# Sheet6.net
KiCad netlist of a schematic drawn in Altium Designer
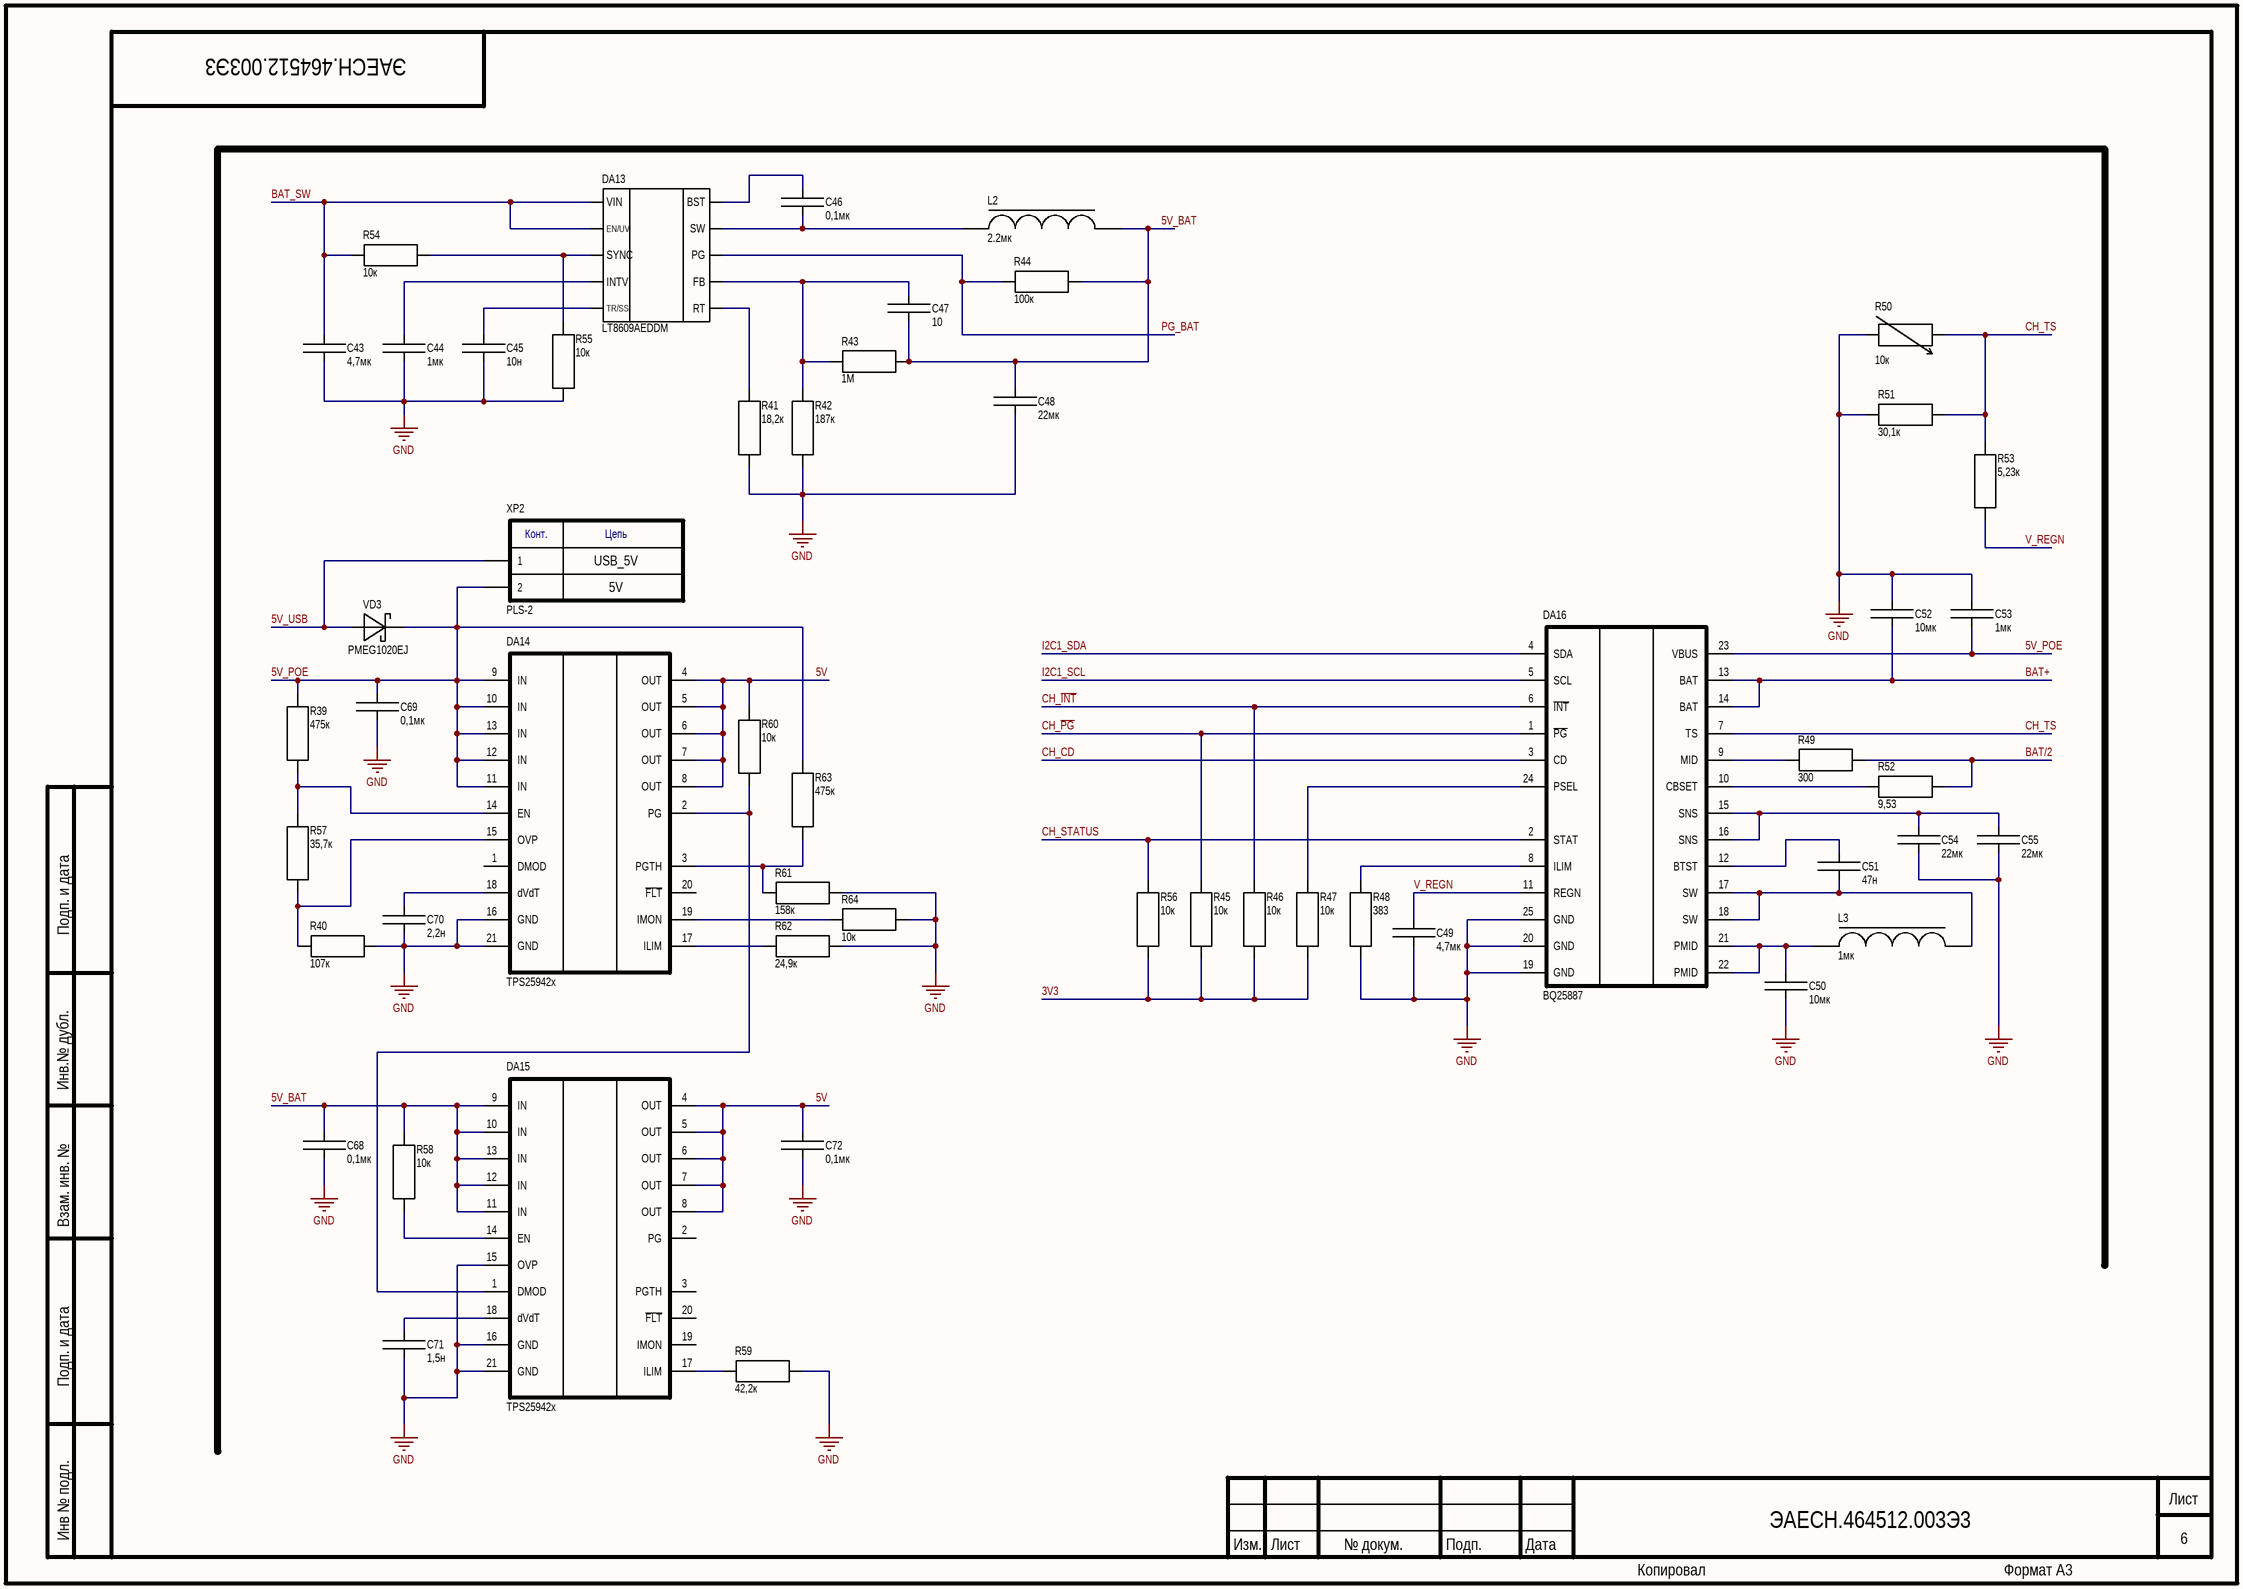
[diagram p0: Sheet6.SchDoc]

(export (version "E")
  (design (tool "Eeschema 10.0.6"))
  (components
    (comp (ref "C43")
      (value "4,7мк")
      (footprint "С0603")
      (fields (field (name "Comment") "C"))
      (libsource (lib "Schlib1") (part "C"))
    )
    (comp (ref "C44")
      (value "1мк")
      (footprint "С0603")
      (fields (field (name "Comment") "C"))
      (libsource (lib "Schlib1") (part "C"))
    )
    (comp (ref "C45")
      (value "10н")
      (footprint "С0603")
      (fields (field (name "Comment") "C"))
      (libsource (lib "Schlib1") (part "C"))
    )
    (comp (ref "C46")
      (value "0,1мк")
      (footprint "С0603")
      (fields (field (name "Comment") "C"))
      (libsource (lib "Schlib1") (part "C"))
    )
    (comp (ref "C47")
      (value "10")
      (footprint "С0603")
      (fields (field (name "Comment") "C"))
      (libsource (lib "Schlib1") (part "C"))
    )
    (comp (ref "C48")
      (value "22мк")
      (footprint "C1206")
      (fields (field (name "Comment") "C"))
      (libsource (lib "Schlib1") (part "C"))
    )
    (comp (ref "C49")
      (value "4,7мк")
      (footprint "С0603")
      (fields (field (name "Comment") "C"))
      (libsource (lib "Schlib1") (part "C"))
    )
    (comp (ref "C50")
      (value "10мк")
      (footprint "С0603")
      (fields (field (name "Comment") "C"))
      (libsource (lib "Schlib1") (part "C"))
    )
    (comp (ref "C51")
      (value "47н")
      (footprint "С0603")
      (fields (field (name "Comment") "C"))
      (libsource (lib "Schlib1") (part "C"))
    )
    (comp (ref "C52")
      (value "10мк")
      (footprint "С0603")
      (fields (field (name "Comment") "C"))
      (libsource (lib "Schlib1") (part "C"))
    )
    (comp (ref "C53")
      (value "1мк")
      (footprint "С0603")
      (fields (field (name "Comment") "C"))
      (libsource (lib "Schlib1") (part "C"))
    )
    (comp (ref "C54")
      (value "22мк")
      (footprint "C1206")
      (fields (field (name "Comment") "C"))
      (libsource (lib "Schlib1") (part "C"))
    )
    (comp (ref "C55")
      (value "22мк")
      (footprint "C1206")
      (fields (field (name "Comment") "C"))
      (libsource (lib "Schlib1") (part "C"))
    )
    (comp (ref "C68")
      (value "0,1мк")
      (footprint "С0603")
      (fields (field (name "Comment") "C"))
      (libsource (lib "Schlib1") (part "C"))
    )
    (comp (ref "C69")
      (value "0,1мк")
      (footprint "С0603")
      (fields (field (name "Comment") "C"))
      (libsource (lib "Schlib1") (part "C"))
    )
    (comp (ref "C70")
      (value "2,2н")
      (footprint "С0603")
      (fields (field (name "Comment") "C"))
      (libsource (lib "Schlib1") (part "C"))
    )
    (comp (ref "C71")
      (value "1,5н")
      (footprint "С0603")
      (fields (field (name "Comment") "C"))
      (libsource (lib "Schlib1") (part "C"))
    )
    (comp (ref "C72")
      (value "0,1мк")
      (footprint "С0603")
      (fields (field (name "Comment") "C"))
      (libsource (lib "Schlib1") (part "C"))
    )
    (comp (ref "DA13")
      (value "LT8609AEDDM")
      (footprint "SON-10")
      (libsource (lib "Schlib1") (part "LT8609AEDDM"))
    )
    (comp (ref "DA14")
      (value "TPS25942x")
      (footprint "WQFN-20")
      (libsource (lib "Schlib1") (part "TPS25942x"))
    )
    (comp (ref "DA15")
      (value "TPS25942x")
      (footprint "WQFN-20")
      (libsource (lib "Schlib1") (part "TPS25942x"))
    )
    (comp (ref "DA16") (value "BQ25887") (footprint "VQFN-24") (libsource (lib "Schlib1") (part "BQ25887")))
    (comp (ref "L2")
      (value "2.2мк")
      (footprint "IND_6.5x6.5_VISHAY")
      (fields (field (name "PARTNUMBER") "IHLP2525CZER2R2MA1"))
      (libsource (lib "Schlib1") (part "L"))
    )
    (comp (ref "L3")
      (value "1мк")
      (footprint "IND_6.5x6.5_VISHAY")
      (fields (field (name "PARTNUMBER") "IHLP2525CZER1R0M01"))
      (libsource (lib "Schlib1") (part "L"))
    )
    (comp (ref "R39")
      (value "475к")
      (footprint "R0603")
      (fields (field (name "Comment") "R"))
      (libsource (lib "Schlib1") (part "R"))
    )
    (comp (ref "R40")
      (value "107к")
      (footprint "R0603")
      (fields (field (name "Comment") "R"))
      (libsource (lib "Schlib1") (part "R"))
    )
    (comp (ref "R41")
      (value "18,2к")
      (footprint "R0603")
      (fields (field (name "Comment") "R"))
      (libsource (lib "Schlib1") (part "R"))
    )
    (comp (ref "R42")
      (value "187к")
      (footprint "R0603")
      (fields (field (name "Comment") "R"))
      (libsource (lib "Schlib1") (part "R"))
    )
    (comp (ref "R43")
      (value "1М")
      (footprint "R0603")
      (fields (field (name "Comment") "R"))
      (libsource (lib "Schlib1") (part "R"))
    )
    (comp (ref "R44")
      (value "100к")
      (footprint "R0603")
      (fields (field (name "Comment") "R"))
      (libsource (lib "Schlib1") (part "R"))
    )
    (comp (ref "R45")
      (value "10к")
      (footprint "R0603")
      (fields (field (name "Comment") "R"))
      (libsource (lib "Schlib1") (part "R"))
    )
    (comp (ref "R46")
      (value "10к")
      (footprint "R0603")
      (fields (field (name "Comment") "R"))
      (libsource (lib "Schlib1") (part "R"))
    )
    (comp (ref "R47")
      (value "10к")
      (footprint "R0603")
      (fields (field (name "Comment") "R"))
      (libsource (lib "Schlib1") (part "R"))
    )
    (comp (ref "R48")
      (value "383")
      (footprint "R0603")
      (fields (field (name "Comment") "R"))
      (libsource (lib "Schlib1") (part "R"))
    )
    (comp (ref "R49")
      (value "300")
      (footprint "R0603")
      (fields (field (name "Comment") "R"))
      (libsource (lib "Schlib1") (part "R"))
    )
    (comp (ref "R50")
      (value "10к")
      (footprint "R0603")
      (fields (field (name "Comment") "EWTF03-103H3T-N"))
      (libsource (lib "Schlib1") (part "R_term_n"))
    )
    (comp (ref "R51")
      (value "30,1к")
      (footprint "R0603")
      (fields (field (name "Comment") "R"))
      (libsource (lib "Schlib1") (part "R"))
    )
    (comp (ref "R52")
      (value "9,53")
      (footprint "R0603")
      (fields (field (name "Comment") "R"))
      (libsource (lib "Schlib1") (part "R"))
    )
    (comp (ref "R53")
      (value "5,23к")
      (footprint "R0603")
      (fields (field (name "Comment") "R"))
      (libsource (lib "Schlib1") (part "R"))
    )
    (comp (ref "R54")
      (value "10к")
      (footprint "R0603")
      (fields (field (name "Comment") "R"))
      (libsource (lib "Schlib1") (part "R"))
    )
    (comp (ref "R55")
      (value "10к")
      (footprint "R0603")
      (fields (field (name "Comment") "R"))
      (libsource (lib "Schlib1") (part "R"))
    )
    (comp (ref "R56")
      (value "10к")
      (footprint "R0603")
      (fields (field (name "Comment") "R"))
      (libsource (lib "Schlib1") (part "R"))
    )
    (comp (ref "R57")
      (value "35,7к")
      (footprint "R0603")
      (fields (field (name "Comment") "R"))
      (libsource (lib "Schlib1") (part "R"))
    )
    (comp (ref "R58")
      (value "10к")
      (footprint "R0603")
      (fields (field (name "Comment") "R"))
      (libsource (lib "Schlib1") (part "R"))
    )
    (comp (ref "R59")
      (value "42,2к")
      (footprint "R0603")
      (fields (field (name "Comment") "R"))
      (libsource (lib "Schlib1") (part "R"))
    )
    (comp (ref "R60")
      (value "10к")
      (footprint "R0603")
      (fields (field (name "Comment") "R"))
      (libsource (lib "Schlib1") (part "R"))
    )
    (comp (ref "R61")
      (value "158к")
      (footprint "R0603")
      (fields (field (name "Comment") "R"))
      (libsource (lib "Schlib1") (part "R"))
    )
    (comp (ref "R62")
      (value "24,9к")
      (footprint "R0603")
      (fields (field (name "Comment") "R"))
      (libsource (lib "Schlib1") (part "R"))
    )
    (comp (ref "R63")
      (value "475к")
      (footprint "R0603")
      (fields (field (name "Comment") "R"))
      (libsource (lib "Schlib1") (part "R"))
    )
    (comp (ref "R64")
      (value "10к")
      (footprint "R0603")
      (fields (field (name "Comment") "R"))
      (libsource (lib "Schlib1") (part "R"))
    )
    (comp (ref "VD3") (value "PMEG1020EJ") (footprint "SOD323F") (libsource (lib "Schlib1") (part "VD_sh")))
    (comp (ref "XP2") (value "PLS-2") (footprint "PLS-2") (libsource (lib "Schlib1") (part "2pin")))
  )
  (nets
    (net (code "1") (name "/3V3") (class "Default")
      (node (ref "R45") (pin "2") (pinfunction "2_2") (pintype "passive"))
      (node (ref "R46") (pin "2") (pinfunction "2_2") (pintype "passive"))
      (node (ref "R47") (pin "2") (pinfunction "2_2") (pintype "passive"))
      (node (ref "R56") (pin "2") (pinfunction "2_2") (pintype "passive"))
    )
    (net (code "2") (name "/5V") (class "Default")
      (node (ref "C72") (pin "1") (pinfunction "1_1") (pintype "passive"))
      (node (ref "DA14") (pin "4") (pinfunction "OUT_4") (pintype "passive"))
      (node (ref "DA14") (pin "5") (pinfunction "OUT_5") (pintype "passive"))
      (node (ref "DA14") (pin "6") (pinfunction "OUT_6") (pintype "passive"))
      (node (ref "DA14") (pin "7") (pinfunction "OUT_7") (pintype "passive"))
      (node (ref "DA14") (pin "8") (pinfunction "OUT_8") (pintype "passive"))
      (node (ref "DA15") (pin "4") (pinfunction "OUT_4") (pintype "passive"))
      (node (ref "DA15") (pin "5") (pinfunction "OUT_5") (pintype "passive"))
      (node (ref "DA15") (pin "6") (pinfunction "OUT_6") (pintype "passive"))
      (node (ref "DA15") (pin "7") (pinfunction "OUT_7") (pintype "passive"))
      (node (ref "DA15") (pin "8") (pinfunction "OUT_8") (pintype "passive"))
      (node (ref "R60") (pin "2") (pinfunction "2_2") (pintype "passive"))
    )
    (net (code "3") (name "/5V_BAT") (class "Default")
      (node (ref "C47") (pin "1") (pinfunction "1_1") (pintype "passive"))
      (node (ref "C48") (pin "1") (pinfunction "1_1") (pintype "passive"))
      (node (ref "C68") (pin "1") (pinfunction "1_1") (pintype "passive"))
      (node (ref "DA15") (pin "10") (pinfunction "IN_10") (pintype "passive"))
      (node (ref "DA15") (pin "11") (pinfunction "IN_11") (pintype "passive"))
      (node (ref "DA15") (pin "12") (pinfunction "IN_12") (pintype "passive"))
      (node (ref "DA15") (pin "13") (pinfunction "IN_13") (pintype "passive"))
      (node (ref "DA15") (pin "9") (pinfunction "IN_9") (pintype "passive"))
      (node (ref "L2") (pin "1") (pinfunction "1_1") (pintype "passive"))
      (node (ref "R43") (pin "2") (pinfunction "2_2") (pintype "passive"))
      (node (ref "R44") (pin "1") (pinfunction "1_1") (pintype "passive"))
      (node (ref "R58") (pin "2") (pinfunction "2_2") (pintype "passive"))
    )
    (net (code "4") (name "/5V_POE") (class "Default")
      (node (ref "C53") (pin "2") (pinfunction "2_2") (pintype "passive"))
      (node (ref "C69") (pin "1") (pinfunction "1_1") (pintype "passive"))
      (node (ref "DA14") (pin "10") (pinfunction "IN_10") (pintype "passive"))
      (node (ref "DA14") (pin "11") (pinfunction "IN_11") (pintype "passive"))
      (node (ref "DA14") (pin "12") (pinfunction "IN_12") (pintype "passive"))
      (node (ref "DA14") (pin "13") (pinfunction "IN_13") (pintype "passive"))
      (node (ref "DA14") (pin "9") (pinfunction "IN_9") (pintype "passive"))
      (node (ref "DA16") (pin "23") (pinfunction "VBUS_23") (pintype "passive"))
      (node (ref "R39") (pin "2") (pinfunction "2_2") (pintype "passive"))
      (node (ref "R63") (pin "2") (pinfunction "2_2") (pintype "passive"))
      (node (ref "VD3") (pin "1") (pinfunction "C_1") (pintype "passive"))
      (node (ref "XP2") (pin "2") (pinfunction "2_2") (pintype "passive"))
    )
    (net (code "5") (name "/5V_USB") (class "Default")
      (node (ref "VD3") (pin "2") (pinfunction "A_2") (pintype "passive"))
      (node (ref "XP2") (pin "1") (pinfunction "1_1") (pintype "passive"))
    )
    (net (code "6") (name "/BAT+") (class "Default")
      (node (ref "C52") (pin "2") (pinfunction "2_2") (pintype "passive"))
      (node (ref "DA16") (pin "13") (pinfunction "BAT_13") (pintype "passive"))
      (node (ref "DA16") (pin "14") (pinfunction "BAT_14") (pintype "passive"))
    )
    (net (code "7") (name "/BAT_SW") (class "Default")
      (node (ref "C43") (pin "1") (pinfunction "1_1") (pintype "passive"))
      (node (ref "DA13") (pin "10") (pinfunction "EN/UV_10") (pintype "passive"))
      (node (ref "DA13") (pin "9") (pinfunction "VIN_9") (pintype "passive"))
      (node (ref "R54") (pin "1") (pinfunction "1_1") (pintype "passive"))
    )
    (net (code "8") (name "/BAT{slash}2") (class "Default")
      (node (ref "R49") (pin "2") (pinfunction "2_2") (pintype "passive"))
      (node (ref "R52") (pin "2") (pinfunction "2_2") (pintype "passive"))
    )
    (net (code "9") (name "/CH_CD") (class "Default")
      (node (ref "DA16") (pin "3") (pinfunction "CD_3") (pintype "passive"))
    )
    (net (code "10") (name "/CH_STATUS") (class "Default")
      (node (ref "DA16") (pin "2") (pinfunction "STAT_2") (pintype "passive"))
      (node (ref "R56") (pin "1") (pinfunction "1_1") (pintype "passive"))
    )
    (net (code "11") (name "/CH_TS") (class "Default")
      (node (ref "DA16") (pin "7") (pinfunction "TS_7") (pintype "passive"))
      (node (ref "R50") (pin "2") (pinfunction "2_2") (pintype "passive"))
      (node (ref "R51") (pin "2") (pinfunction "2_2") (pintype "passive"))
      (node (ref "R53") (pin "1") (pinfunction "1_1") (pintype "passive"))
    )
    (net (code "12") (name "/CH_~{INT}") (class "Default")
      (node (ref "DA16") (pin "6") (pinfunction "~{INT}_6") (pintype "passive"))
      (node (ref "R46") (pin "1") (pinfunction "1_1") (pintype "passive"))
    )
    (net (code "13") (name "/CH_~{PG}") (class "Default")
      (node (ref "DA16") (pin "1") (pinfunction "~{PG}_1") (pintype "passive"))
      (node (ref "R45") (pin "1") (pinfunction "1_1") (pintype "passive"))
    )
    (net (code "14") (name "/I2C1_SCL") (class "Default")
      (node (ref "DA16") (pin "5") (pinfunction "SCL_5") (pintype "passive"))
    )
    (net (code "15") (name "/I2C1_SDA") (class "Default")
      (node (ref "DA16") (pin "4") (pinfunction "SDA_4") (pintype "passive"))
    )
    (net (code "16") (name "/PG_BAT") (class "Default")
      (node (ref "DA13") (pin "8") (pinfunction "PG_8") (pintype "passive"))
      (node (ref "R44") (pin "2") (pinfunction "2_2") (pintype "passive"))
    )
    (net (code "17") (name "/V_REGN") (class "Default")
      (node (ref "C49") (pin "1") (pinfunction "1_1") (pintype "passive"))
      (node (ref "DA16") (pin "11") (pinfunction "REGN_11") (pintype "passive"))
      (node (ref "R53") (pin "2") (pinfunction "2_2") (pintype "passive"))
    )
    (net (code "18") (name "GND") (class "Default")
      (node (ref "C43") (pin "2") (pinfunction "2_2") (pintype "passive"))
      (node (ref "C44") (pin "2") (pinfunction "2_2") (pintype "passive"))
      (node (ref "C45") (pin "2") (pinfunction "2_2") (pintype "passive"))
      (node (ref "C48") (pin "2") (pinfunction "2_2") (pintype "passive"))
      (node (ref "C49") (pin "2") (pinfunction "2_2") (pintype "passive"))
      (node (ref "C50") (pin "2") (pinfunction "2_2") (pintype "passive"))
      (node (ref "C52") (pin "1") (pinfunction "1_1") (pintype "passive"))
      (node (ref "C53") (pin "1") (pinfunction "1_1") (pintype "passive"))
      (node (ref "C54") (pin "2") (pinfunction "2_2") (pintype "passive"))
      (node (ref "C55") (pin "2") (pinfunction "2_2") (pintype "passive"))
      (node (ref "C68") (pin "2") (pinfunction "2_2") (pintype "passive"))
      (node (ref "C69") (pin "2") (pinfunction "2_2") (pintype "passive"))
      (node (ref "C70") (pin "2") (pinfunction "2_2") (pintype "passive"))
      (node (ref "C71") (pin "2") (pinfunction "2_2") (pintype "passive"))
      (node (ref "C72") (pin "2") (pinfunction "2_2") (pintype "passive"))
      (node (ref "DA14") (pin "16") (pinfunction "GND_16") (pintype "passive"))
      (node (ref "DA14") (pin "21") (pinfunction "GND_21") (pintype "passive"))
      (node (ref "DA15") (pin "15") (pinfunction "OVP_15") (pintype "passive"))
      (node (ref "DA15") (pin "16") (pinfunction "GND_16") (pintype "passive"))
      (node (ref "DA15") (pin "21") (pinfunction "GND_21") (pintype "passive"))
      (node (ref "DA16") (pin "19") (pinfunction "GND_19") (pintype "passive"))
      (node (ref "DA16") (pin "20") (pinfunction "GND_20") (pintype "passive"))
      (node (ref "DA16") (pin "25") (pinfunction "GND_25") (pintype "passive"))
      (node (ref "R40") (pin "2") (pinfunction "2_2") (pintype "passive"))
      (node (ref "R41") (pin "1") (pinfunction "1_1") (pintype "passive"))
      (node (ref "R42") (pin "2") (pinfunction "2_2") (pintype "passive"))
      (node (ref "R48") (pin "1") (pinfunction "1_1") (pintype "passive"))
      (node (ref "R50") (pin "1") (pinfunction "1_1") (pintype "passive"))
      (node (ref "R51") (pin "1") (pinfunction "1_1") (pintype "passive"))
      (node (ref "R55") (pin "1") (pinfunction "1_1") (pintype "passive"))
      (node (ref "R59") (pin "2") (pinfunction "2_2") (pintype "passive"))
      (node (ref "R61") (pin "1") (pinfunction "1_1") (pintype "passive"))
      (node (ref "R62") (pin "2") (pinfunction "2_2") (pintype "passive"))
      (node (ref "R64") (pin "1") (pinfunction "1_1") (pintype "passive"))
    )
    (net (code "19") (name "Net-(C50-Pad1)") (class "Default")
      (node (ref "C50") (pin "1") (pinfunction "1_1") (pintype "passive"))
      (node (ref "DA16") (pin "21") (pinfunction "PMID_21") (pintype "passive"))
      (node (ref "DA16") (pin "22") (pinfunction "PMID_22") (pintype "passive"))
      (node (ref "L3") (pin "2") (pinfunction "2_2") (pintype "passive"))
    )
    (net (code "20") (name "Net-(C51-Pad2)") (class "Default")
      (node (ref "C51") (pin "2") (pinfunction "2_2") (pintype "passive"))
      (node (ref "DA16") (pin "17") (pinfunction "SW_17") (pintype "passive"))
      (node (ref "DA16") (pin "18") (pinfunction "SW_18") (pintype "passive"))
      (node (ref "L3") (pin "1") (pinfunction "1_1") (pintype "passive"))
    )
    (net (code "21") (name "Net-(C54-Pad1)") (class "Default")
      (node (ref "C54") (pin "1") (pinfunction "1_1") (pintype "passive"))
      (node (ref "C55") (pin "1") (pinfunction "1_1") (pintype "passive"))
      (node (ref "DA16") (pin "15") (pinfunction "SNS_15") (pintype "passive"))
      (node (ref "DA16") (pin "16") (pinfunction "SNS_16") (pintype "passive"))
    )
    (net (code "22") (name "Net-(DA13-BST)") (class "Default")
      (node (ref "C46") (pin "1") (pinfunction "1_1") (pintype "passive"))
      (node (ref "DA13") (pin "1") (pinfunction "BST_1") (pintype "passive"))
    )
    (net (code "23") (name "Net-(DA13-FB)") (class "Default")
      (node (ref "C47") (pin "2") (pinfunction "2_2") (pintype "passive"))
      (node (ref "DA13") (pin "6") (pinfunction "FB_6") (pintype "passive"))
      (node (ref "R42") (pin "1") (pinfunction "1_1") (pintype "passive"))
      (node (ref "R43") (pin "1") (pinfunction "1_1") (pintype "passive"))
    )
    (net (code "24") (name "Net-(DA13-INTV)") (class "Default")
      (node (ref "C44") (pin "1") (pinfunction "1_1") (pintype "passive"))
      (node (ref "DA13") (pin "3") (pinfunction "INTV_3") (pintype "passive"))
    )
    (net (code "25") (name "Net-(DA13-RT)") (class "Default")
      (node (ref "DA13") (pin "4") (pinfunction "RT_4") (pintype "passive"))
      (node (ref "R41") (pin "2") (pinfunction "2_2") (pintype "passive"))
    )
    (net (code "26") (name "Net-(DA13-SW)") (class "Default")
      (node (ref "C46") (pin "2") (pinfunction "2_2") (pintype "passive"))
      (node (ref "DA13") (pin "2") (pinfunction "SW_2") (pintype "passive"))
      (node (ref "L2") (pin "2") (pinfunction "2_2") (pintype "passive"))
    )
    (net (code "27") (name "Net-(DA13-SYNC)") (class "Default")
      (node (ref "DA13") (pin "5") (pinfunction "SYNC_5") (pintype "passive"))
      (node (ref "R54") (pin "2") (pinfunction "2_2") (pintype "passive"))
      (node (ref "R55") (pin "2") (pinfunction "2_2") (pintype "passive"))
    )
    (net (code "28") (name "Net-(DA13-TR{slash}SS)") (class "Default")
      (node (ref "C45") (pin "1") (pinfunction "1_1") (pintype "passive"))
      (node (ref "DA13") (pin "7") (pinfunction "TR/SS_7") (pintype "passive"))
    )
    (net (code "29") (name "Net-(DA14-EN)") (class "Default")
      (node (ref "DA14") (pin "14") (pinfunction "EN_14") (pintype "passive"))
      (node (ref "R39") (pin "1") (pinfunction "1_1") (pintype "passive"))
      (node (ref "R57") (pin "2") (pinfunction "2_2") (pintype "passive"))
    )
    (net (code "30") (name "Net-(DA14-ILIM)") (class "Default")
      (node (ref "DA14") (pin "17") (pinfunction "ILIM_17") (pintype "passive"))
      (node (ref "R62") (pin "1") (pinfunction "1_1") (pintype "passive"))
    )
    (net (code "31") (name "Net-(DA14-IMON)") (class "Default")
      (node (ref "DA14") (pin "19") (pinfunction "IMON_19") (pintype "passive"))
      (node (ref "R64") (pin "2") (pinfunction "2_2") (pintype "passive"))
    )
    (net (code "32") (name "Net-(DA14-OVP)") (class "Default")
      (node (ref "DA14") (pin "15") (pinfunction "OVP_15") (pintype "passive"))
      (node (ref "R40") (pin "1") (pinfunction "1_1") (pintype "passive"))
      (node (ref "R57") (pin "1") (pinfunction "1_1") (pintype "passive"))
    )
    (net (code "33") (name "Net-(DA14-PG)") (class "Default")
      (node (ref "DA14") (pin "2") (pinfunction "PG_2") (pintype "passive"))
      (node (ref "DA15") (pin "1") (pinfunction "DMOD_1") (pintype "passive"))
      (node (ref "R60") (pin "1") (pinfunction "1_1") (pintype "passive"))
    )
    (net (code "34") (name "Net-(DA14-PGTH)") (class "Default")
      (node (ref "DA14") (pin "3") (pinfunction "PGTH_3") (pintype "passive"))
      (node (ref "R61") (pin "2") (pinfunction "2_2") (pintype "passive"))
      (node (ref "R63") (pin "1") (pinfunction "1_1") (pintype "passive"))
    )
    (net (code "35") (name "Net-(DA14-dVdT)") (class "Default")
      (node (ref "C70") (pin "1") (pinfunction "1_1") (pintype "passive"))
      (node (ref "DA14") (pin "18") (pinfunction "dVdT_18") (pintype "passive"))
    )
    (net (code "36") (name "Net-(DA15-EN)") (class "Default")
      (node (ref "DA15") (pin "14") (pinfunction "EN_14") (pintype "passive"))
      (node (ref "R58") (pin "1") (pinfunction "1_1") (pintype "passive"))
    )
    (net (code "37") (name "Net-(DA15-ILIM)") (class "Default")
      (node (ref "DA15") (pin "17") (pinfunction "ILIM_17") (pintype "passive"))
      (node (ref "R59") (pin "1") (pinfunction "1_1") (pintype "passive"))
    )
    (net (code "38") (name "Net-(DA15-dVdT)") (class "Default")
      (node (ref "C71") (pin "1") (pinfunction "1_1") (pintype "passive"))
      (node (ref "DA15") (pin "18") (pinfunction "dVdT_18") (pintype "passive"))
    )
    (net (code "39") (name "Net-(DA16-BTST)") (class "Default")
      (node (ref "C51") (pin "1") (pinfunction "1_1") (pintype "passive"))
      (node (ref "DA16") (pin "12") (pinfunction "BTST_12") (pintype "passive"))
    )
    (net (code "40") (name "Net-(DA16-CBSET)") (class "Default")
      (node (ref "DA16") (pin "10") (pinfunction "CBSET_10") (pintype "passive"))
      (node (ref "R52") (pin "1") (pinfunction "1_1") (pintype "passive"))
    )
    (net (code "41") (name "Net-(DA16-ILIM)") (class "Default")
      (node (ref "DA16") (pin "8") (pinfunction "ILIM_8") (pintype "passive"))
      (node (ref "R48") (pin "2") (pinfunction "2_2") (pintype "passive"))
    )
    (net (code "42") (name "Net-(DA16-MID)") (class "Default")
      (node (ref "DA16") (pin "9") (pinfunction "MID_9") (pintype "passive"))
      (node (ref "R49") (pin "1") (pinfunction "1_1") (pintype "passive"))
    )
    (net (code "43") (name "Net-(DA16-PSEL)") (class "Default")
      (node (ref "DA16") (pin "24") (pinfunction "PSEL_24") (pintype "passive"))
      (node (ref "R47") (pin "1") (pinfunction "1_1") (pintype "passive"))
    )
    (net (code "44") (name "unconnected-(DA14-DMOD-Pad1)") (class "Default")
      (node (ref "DA14") (pin "1") (pinfunction "DMOD_1") (pintype "passive"))
    )
    (net (code "45") (name "unconnected-(DA14-~{FLT}-Pad20)") (class "Default")
      (node (ref "DA14") (pin "20") (pinfunction "~{FLT}_20") (pintype "passive"))
    )
    (net (code "46") (name "unconnected-(DA15-IMON-Pad19)") (class "Default")
      (node (ref "DA15") (pin "19") (pinfunction "IMON_19") (pintype "passive"))
    )
    (net (code "47") (name "unconnected-(DA15-PG-Pad2)") (class "Default")
      (node (ref "DA15") (pin "2") (pinfunction "PG_2") (pintype "passive"))
    )
    (net (code "48") (name "unconnected-(DA15-PGTH-Pad3)") (class "Default")
      (node (ref "DA15") (pin "3") (pinfunction "PGTH_3") (pintype "passive"))
    )
    (net (code "49") (name "unconnected-(DA15-~{FLT}-Pad20)") (class "Default")
      (node (ref "DA15") (pin "20") (pinfunction "~{FLT}_20") (pintype "passive"))
    )
  )
)
